# power_amplifier.net
KiCad netlist of a schematic drawn in Altium Designer
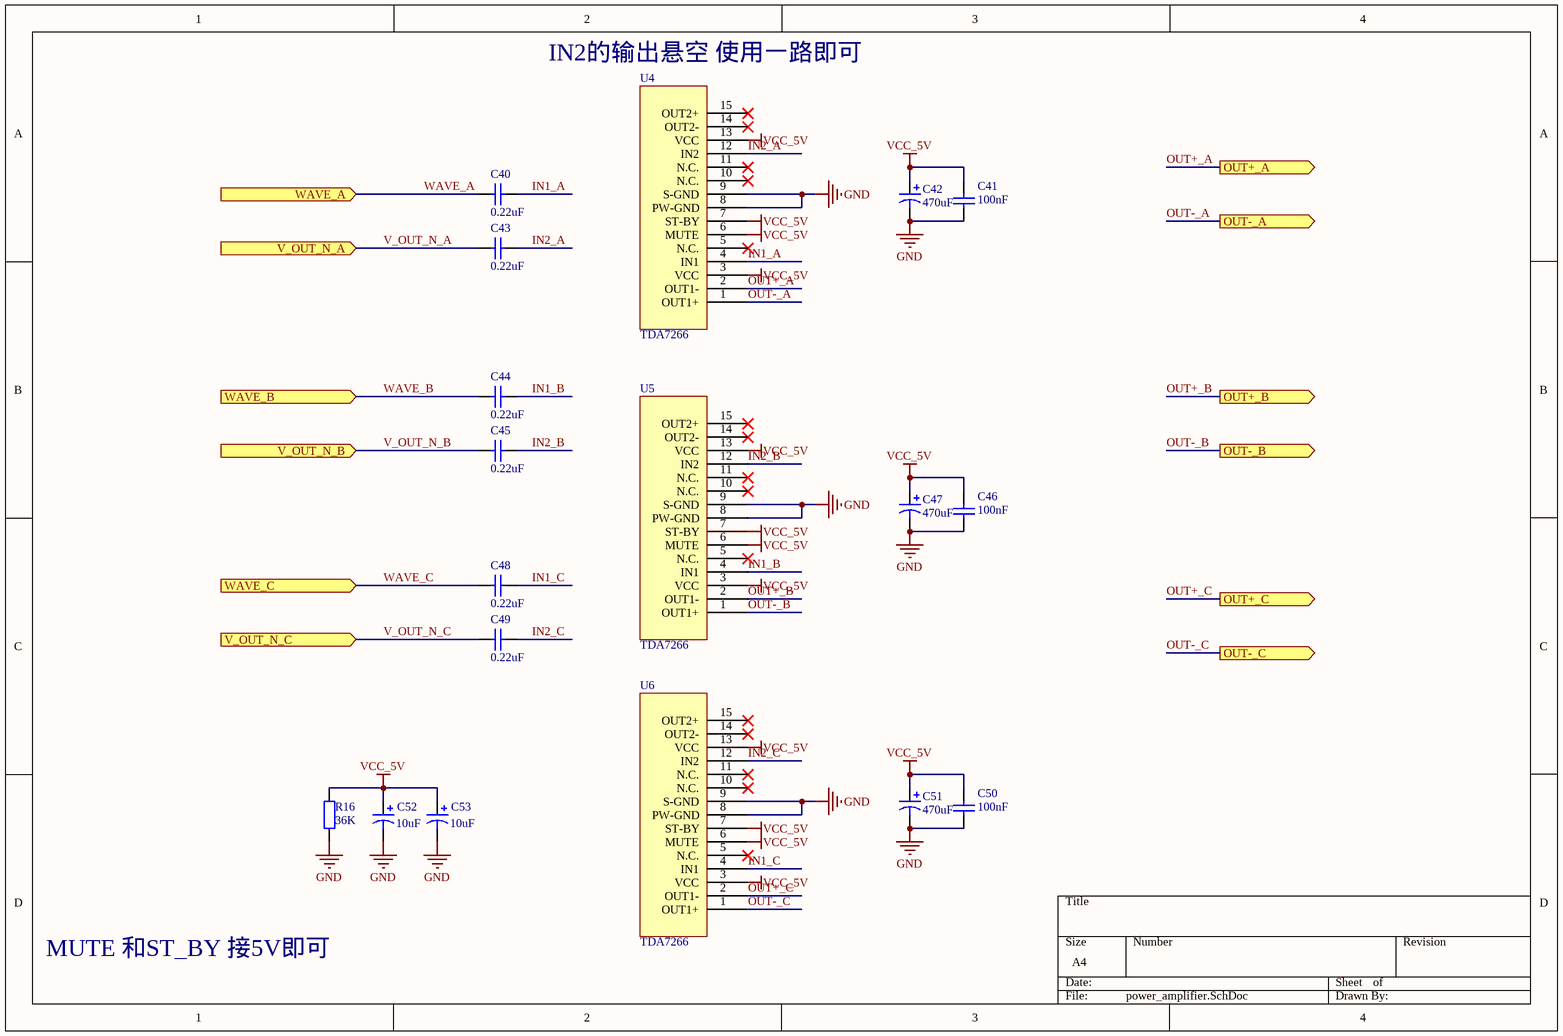
[diagram p0: power_amplifier.SchDoc]

(export (version "E")
  (design (tool "Eeschema 10.0.6"))
  (components
    (comp (ref "C40")
      (value "0.22uF")
      (footprint "0805")
      (fields
        (field (name "Comment") "Cap")
        (field (name "原理图绘制者") "刘永钦")
        (field (name "原理图提供者") "刘永钦")
        (field (name "原理图审核人1") "徐鹏飞")
        (field (name "封装0805绘制者") "刘永钦")
        (field (name "封装0805提供者") "刘永钦")
        (field (name "封装0805审核人1") "徐鹏飞")
        (field (name "原理图审核人2") "朱觉文")
        (field (name "封装0805审核人2") "朱觉文")
        (field (name "封装0603绘制者") "刘永钦")
        (field (name "封装0603提供者") "刘永钦")
        (field (name "封装0603审核人1") "朱觉文")
        (field (name "封装0603审核人2") "徐鹏飞")
      )
      (libsource (lib "自动化研究所集成库20170318") (part "Cap"))
    )
    (comp (ref "C41")
      (value "100nF")
      (footprint "0805")
      (fields
        (field (name "Comment") "Cap")
        (field (name "原理图绘制者") "刘永钦")
        (field (name "原理图提供者") "刘永钦")
        (field (name "原理图审核人1") "徐鹏飞")
        (field (name "封装0805绘制者") "刘永钦")
        (field (name "封装0805提供者") "刘永钦")
        (field (name "封装0805审核人1") "徐鹏飞")
        (field (name "原理图审核人2") "朱觉文")
        (field (name "封装0805审核人2") "朱觉文")
        (field (name "封装0603绘制者") "刘永钦")
        (field (name "封装0603提供者") "刘永钦")
        (field (name "封装0603审核人1") "朱觉文")
        (field (name "封装0603审核人2") "徐鹏飞")
      )
      (libsource (lib "自动化研究所集成库20170318") (part "Cap"))
    )
    (comp (ref "C42")
      (value "470uF")
      (footprint "cap贴片铝电解质470uF 16V")
      (fields
        (field (name "Comment") "Cap Poll")
        (field (name "原理图绘制者") "刘永钦")
        (field (name "原理图提供者") "刘永钦")
        (field (name "原理图审核人1") "徐鹏飞")
        (field (name "封装CAP 钽 7343 E绘制者") "刘永钦")
        (field (name "封装CAP 钽 7343 E提供者") "刘永钦")
        (field (name "封装CAP 钽 7343 E审核人1") "徐鹏飞")
        (field (name "封装CAP贴片铝电解质470UF 16V绘制者") "李泽")
        (field (name "封装CAP贴片铝电解质470UF 16V提供者") "刘永钦")
        (field (name "封装CAP贴片铝电解质470UF 16V审核人1") "徐鹏飞")
        (field (name "封装CAP 3528B绘制者") "陈汉诚")
        (field (name "封装CAP 3528B提供者") "刘永钦")
        (field (name "封装CAP 3528B审核人1") "徐鹏飞")
        (field (name "封装CAP直插 10UF 50V提供者") "刘永钦")
        (field (name "封装CAP直插 10UF 50V审核人1") "徐鹏飞")
        (field (name "封装CAP 3528B审核人2") "朱觉文")
        (field (name "封装CAP直插 10UF 50V审核人2") "朱觉文")
        (field (name "封装CAP贴片铝电解质470UF 16V审核人2") "朱觉文")
        (field (name "封装CAP 钽 7343 E审核人2") "朱觉文")
        (field (name "原理图审核人2") "朱觉文")
      )
      (libsource (lib "自动化研究所集成库20170318") (part "Cap Poll"))
    )
    (comp (ref "C43")
      (value "0.22uF")
      (footprint "0805")
      (fields
        (field (name "Comment") "Cap")
        (field (name "原理图绘制者") "刘永钦")
        (field (name "原理图提供者") "刘永钦")
        (field (name "原理图审核人1") "徐鹏飞")
        (field (name "封装0805绘制者") "刘永钦")
        (field (name "封装0805提供者") "刘永钦")
        (field (name "封装0805审核人1") "徐鹏飞")
        (field (name "原理图审核人2") "朱觉文")
        (field (name "封装0805审核人2") "朱觉文")
        (field (name "封装0603绘制者") "刘永钦")
        (field (name "封装0603提供者") "刘永钦")
        (field (name "封装0603审核人1") "朱觉文")
        (field (name "封装0603审核人2") "徐鹏飞")
      )
      (libsource (lib "自动化研究所集成库20170318") (part "Cap"))
    )
    (comp (ref "C44")
      (value "0.22uF")
      (footprint "0805")
      (fields
        (field (name "Comment") "Cap")
        (field (name "原理图绘制者") "刘永钦")
        (field (name "原理图提供者") "刘永钦")
        (field (name "原理图审核人1") "徐鹏飞")
        (field (name "封装0805绘制者") "刘永钦")
        (field (name "封装0805提供者") "刘永钦")
        (field (name "封装0805审核人1") "徐鹏飞")
        (field (name "原理图审核人2") "朱觉文")
        (field (name "封装0805审核人2") "朱觉文")
        (field (name "封装0603绘制者") "刘永钦")
        (field (name "封装0603提供者") "刘永钦")
        (field (name "封装0603审核人1") "朱觉文")
        (field (name "封装0603审核人2") "徐鹏飞")
      )
      (libsource (lib "自动化研究所集成库20170318") (part "Cap"))
    )
    (comp (ref "C45")
      (value "0.22uF")
      (footprint "0805")
      (fields
        (field (name "Comment") "Cap")
        (field (name "原理图绘制者") "刘永钦")
        (field (name "原理图提供者") "刘永钦")
        (field (name "原理图审核人1") "徐鹏飞")
        (field (name "封装0805绘制者") "刘永钦")
        (field (name "封装0805提供者") "刘永钦")
        (field (name "封装0805审核人1") "徐鹏飞")
        (field (name "原理图审核人2") "朱觉文")
        (field (name "封装0805审核人2") "朱觉文")
        (field (name "封装0603绘制者") "刘永钦")
        (field (name "封装0603提供者") "刘永钦")
        (field (name "封装0603审核人1") "朱觉文")
        (field (name "封装0603审核人2") "徐鹏飞")
      )
      (libsource (lib "自动化研究所集成库20170318") (part "Cap"))
    )
    (comp (ref "C46")
      (value "100nF")
      (footprint "0805")
      (fields
        (field (name "Comment") "Cap")
        (field (name "原理图绘制者") "刘永钦")
        (field (name "原理图提供者") "刘永钦")
        (field (name "原理图审核人1") "徐鹏飞")
        (field (name "封装0805绘制者") "刘永钦")
        (field (name "封装0805提供者") "刘永钦")
        (field (name "封装0805审核人1") "徐鹏飞")
        (field (name "原理图审核人2") "朱觉文")
        (field (name "封装0805审核人2") "朱觉文")
        (field (name "封装0603绘制者") "刘永钦")
        (field (name "封装0603提供者") "刘永钦")
        (field (name "封装0603审核人1") "朱觉文")
        (field (name "封装0603审核人2") "徐鹏飞")
      )
      (libsource (lib "自动化研究所集成库20170318") (part "Cap"))
    )
    (comp (ref "C47")
      (value "470uF")
      (footprint "cap贴片铝电解质470uF 16V")
      (fields
        (field (name "Comment") "Cap Poll")
        (field (name "原理图绘制者") "刘永钦")
        (field (name "原理图提供者") "刘永钦")
        (field (name "原理图审核人1") "徐鹏飞")
        (field (name "封装CAP 钽 7343 E绘制者") "刘永钦")
        (field (name "封装CAP 钽 7343 E提供者") "刘永钦")
        (field (name "封装CAP 钽 7343 E审核人1") "徐鹏飞")
        (field (name "封装CAP贴片铝电解质470UF 16V绘制者") "李泽")
        (field (name "封装CAP贴片铝电解质470UF 16V提供者") "刘永钦")
        (field (name "封装CAP贴片铝电解质470UF 16V审核人1") "徐鹏飞")
        (field (name "封装CAP 3528B绘制者") "陈汉诚")
        (field (name "封装CAP 3528B提供者") "刘永钦")
        (field (name "封装CAP 3528B审核人1") "徐鹏飞")
        (field (name "封装CAP直插 10UF 50V提供者") "刘永钦")
        (field (name "封装CAP直插 10UF 50V审核人1") "徐鹏飞")
        (field (name "封装CAP 3528B审核人2") "朱觉文")
        (field (name "封装CAP直插 10UF 50V审核人2") "朱觉文")
        (field (name "封装CAP贴片铝电解质470UF 16V审核人2") "朱觉文")
        (field (name "封装CAP 钽 7343 E审核人2") "朱觉文")
        (field (name "原理图审核人2") "朱觉文")
      )
      (libsource (lib "自动化研究所集成库20170318") (part "Cap Poll"))
    )
    (comp (ref "C48")
      (value "0.22uF")
      (footprint "0805")
      (fields
        (field (name "Comment") "Cap")
        (field (name "原理图绘制者") "刘永钦")
        (field (name "原理图提供者") "刘永钦")
        (field (name "原理图审核人1") "徐鹏飞")
        (field (name "封装0805绘制者") "刘永钦")
        (field (name "封装0805提供者") "刘永钦")
        (field (name "封装0805审核人1") "徐鹏飞")
        (field (name "原理图审核人2") "朱觉文")
        (field (name "封装0805审核人2") "朱觉文")
        (field (name "封装0603绘制者") "刘永钦")
        (field (name "封装0603提供者") "刘永钦")
        (field (name "封装0603审核人1") "朱觉文")
        (field (name "封装0603审核人2") "徐鹏飞")
      )
      (libsource (lib "自动化研究所集成库20170318") (part "Cap"))
    )
    (comp (ref "C49")
      (value "0.22uF")
      (footprint "0805")
      (fields
        (field (name "Comment") "Cap")
        (field (name "原理图绘制者") "刘永钦")
        (field (name "原理图提供者") "刘永钦")
        (field (name "原理图审核人1") "徐鹏飞")
        (field (name "封装0805绘制者") "刘永钦")
        (field (name "封装0805提供者") "刘永钦")
        (field (name "封装0805审核人1") "徐鹏飞")
        (field (name "原理图审核人2") "朱觉文")
        (field (name "封装0805审核人2") "朱觉文")
        (field (name "封装0603绘制者") "刘永钦")
        (field (name "封装0603提供者") "刘永钦")
        (field (name "封装0603审核人1") "朱觉文")
        (field (name "封装0603审核人2") "徐鹏飞")
      )
      (libsource (lib "自动化研究所集成库20170318") (part "Cap"))
    )
    (comp (ref "C50")
      (value "100nF")
      (footprint "0805")
      (fields
        (field (name "Comment") "Cap")
        (field (name "原理图绘制者") "刘永钦")
        (field (name "原理图提供者") "刘永钦")
        (field (name "原理图审核人1") "徐鹏飞")
        (field (name "封装0805绘制者") "刘永钦")
        (field (name "封装0805提供者") "刘永钦")
        (field (name "封装0805审核人1") "徐鹏飞")
        (field (name "原理图审核人2") "朱觉文")
        (field (name "封装0805审核人2") "朱觉文")
        (field (name "封装0603绘制者") "刘永钦")
        (field (name "封装0603提供者") "刘永钦")
        (field (name "封装0603审核人1") "朱觉文")
        (field (name "封装0603审核人2") "徐鹏飞")
      )
      (libsource (lib "自动化研究所集成库20170318") (part "Cap"))
    )
    (comp (ref "C51")
      (value "470uF")
      (footprint "cap贴片铝电解质470uF 16V")
      (fields
        (field (name "Comment") "Cap Poll")
        (field (name "原理图绘制者") "刘永钦")
        (field (name "原理图提供者") "刘永钦")
        (field (name "原理图审核人1") "徐鹏飞")
        (field (name "封装CAP 钽 7343 E绘制者") "刘永钦")
        (field (name "封装CAP 钽 7343 E提供者") "刘永钦")
        (field (name "封装CAP 钽 7343 E审核人1") "徐鹏飞")
        (field (name "封装CAP贴片铝电解质470UF 16V绘制者") "李泽")
        (field (name "封装CAP贴片铝电解质470UF 16V提供者") "刘永钦")
        (field (name "封装CAP贴片铝电解质470UF 16V审核人1") "徐鹏飞")
        (field (name "封装CAP 3528B绘制者") "陈汉诚")
        (field (name "封装CAP 3528B提供者") "刘永钦")
        (field (name "封装CAP 3528B审核人1") "徐鹏飞")
        (field (name "封装CAP直插 10UF 50V提供者") "刘永钦")
        (field (name "封装CAP直插 10UF 50V审核人1") "徐鹏飞")
        (field (name "封装CAP 3528B审核人2") "朱觉文")
        (field (name "封装CAP直插 10UF 50V审核人2") "朱觉文")
        (field (name "封装CAP贴片铝电解质470UF 16V审核人2") "朱觉文")
        (field (name "封装CAP 钽 7343 E审核人2") "朱觉文")
        (field (name "原理图审核人2") "朱觉文")
      )
      (libsource (lib "自动化研究所集成库20170318") (part "Cap Poll"))
    )
    (comp (ref "C52")
      (value "10uF")
      (footprint "Cap 3528B")
      (fields
        (field (name "Comment") "Cap Poll")
        (field (name "原理图绘制者") "刘永钦")
        (field (name "原理图提供者") "刘永钦")
        (field (name "原理图审核人1") "徐鹏飞")
        (field (name "封装CAP 钽 7343 E绘制者") "刘永钦")
        (field (name "封装CAP 钽 7343 E提供者") "刘永钦")
        (field (name "封装CAP 钽 7343 E审核人1") "徐鹏飞")
        (field (name "封装CAP贴片铝电解质470UF 16V绘制者") "李泽")
        (field (name "封装CAP贴片铝电解质470UF 16V提供者") "刘永钦")
        (field (name "封装CAP贴片铝电解质470UF 16V审核人1") "徐鹏飞")
        (field (name "封装CAP 3528B绘制者") "陈汉诚")
        (field (name "封装CAP 3528B提供者") "刘永钦")
        (field (name "封装CAP 3528B审核人1") "徐鹏飞")
        (field (name "封装CAP直插 10UF 50V提供者") "刘永钦")
        (field (name "封装CAP直插 10UF 50V审核人1") "徐鹏飞")
        (field (name "封装CAP 3528B审核人2") "朱觉文")
        (field (name "封装CAP直插 10UF 50V审核人2") "朱觉文")
        (field (name "封装CAP贴片铝电解质470UF 16V审核人2") "朱觉文")
        (field (name "封装CAP 钽 7343 E审核人2") "朱觉文")
        (field (name "原理图审核人2") "朱觉文")
      )
      (libsource (lib "自动化研究所集成库20170318") (part "Cap Poll"))
    )
    (comp (ref "C53")
      (value "10uF")
      (footprint "Cap 3528B")
      (fields
        (field (name "Comment") "Cap Poll")
        (field (name "原理图绘制者") "刘永钦")
        (field (name "原理图提供者") "刘永钦")
        (field (name "原理图审核人1") "徐鹏飞")
        (field (name "封装CAP 钽 7343 E绘制者") "刘永钦")
        (field (name "封装CAP 钽 7343 E提供者") "刘永钦")
        (field (name "封装CAP 钽 7343 E审核人1") "徐鹏飞")
        (field (name "封装CAP贴片铝电解质470UF 16V绘制者") "李泽")
        (field (name "封装CAP贴片铝电解质470UF 16V提供者") "刘永钦")
        (field (name "封装CAP贴片铝电解质470UF 16V审核人1") "徐鹏飞")
        (field (name "封装CAP 3528B绘制者") "陈汉诚")
        (field (name "封装CAP 3528B提供者") "刘永钦")
        (field (name "封装CAP 3528B审核人1") "徐鹏飞")
        (field (name "封装CAP直插 10UF 50V提供者") "刘永钦")
        (field (name "封装CAP直插 10UF 50V审核人1") "徐鹏飞")
        (field (name "封装CAP 3528B审核人2") "朱觉文")
        (field (name "封装CAP直插 10UF 50V审核人2") "朱觉文")
        (field (name "封装CAP贴片铝电解质470UF 16V审核人2") "朱觉文")
        (field (name "封装CAP 钽 7343 E审核人2") "朱觉文")
        (field (name "原理图审核人2") "朱觉文")
      )
      (libsource (lib "自动化研究所集成库20170318") (part "Cap Poll"))
    )
    (comp (ref "R16")
      (value "36K")
      (footprint "0805")
      (fields
        (field (name "Comment") "Res")
        (field (name "原理图绘制者") "刘永钦")
        (field (name "原理图提供者") "刘永钦")
        (field (name "原理图审核人1") "徐鹏飞")
        (field (name "封装0805绘制者") "刘永钦")
        (field (name "封装0805提供者") "刘永钦")
        (field (name "封装0805审核人1") "徐鹏飞")
        (field (name "原理图审核人2") "朱觉文")
        (field (name "封装0805审核人2") "朱觉文")
        (field (name "封装0603提供者") "刘永钦")
        (field (name "封装0603审核人2") "朱觉文")
        (field (name "封装0603审核人1") "徐鹏飞")
        (field (name "封装2512-RESC6332X06N审核人2") "朱觉文")
        (field (name "封装2512-RESC6332X06N提供者") "刘永钦")
        (field (name "封装2512-RESC6332X06N审核人1") "徐鹏飞")
        (field (name "封装0603绘制者") "刘永钦")
        (field (name "封装2512-RESC6332X06N绘制者") "刘永钦")
      )
      (libsource (lib "自动化研究所集成库20170318") (part "Res"))
    )
    (comp (ref "U4") (value "TDA7266") (footprint "TDA7266") (libsource (lib "Dugu") (part "TDA7266")))
    (comp (ref "U5") (value "TDA7266") (footprint "TDA7266") (libsource (lib "Dugu") (part "TDA7266")))
    (comp (ref "U6") (value "TDA7266") (footprint "TDA7266") (libsource (lib "Dugu") (part "TDA7266")))
  )
  (nets
    (net (code "1") (name "/IN1_A") (class "Default")
      (node (ref "C40") (pin "2") (pinfunction "2_2") (pintype "passive"))
      (node (ref "U4") (pin "4") (pinfunction "IN1_4") (pintype "passive"))
    )
    (net (code "2") (name "/IN1_B") (class "Default")
      (node (ref "C44") (pin "2") (pinfunction "2_2") (pintype "passive"))
      (node (ref "U5") (pin "4") (pinfunction "IN1_4") (pintype "passive"))
    )
    (net (code "3") (name "/IN1_C") (class "Default")
      (node (ref "C48") (pin "2") (pinfunction "2_2") (pintype "passive"))
      (node (ref "U6") (pin "4") (pinfunction "IN1_4") (pintype "passive"))
    )
    (net (code "4") (name "/IN2_A") (class "Default")
      (node (ref "C43") (pin "2") (pinfunction "2_2") (pintype "passive"))
      (node (ref "U4") (pin "12") (pinfunction "IN2_12") (pintype "passive"))
    )
    (net (code "5") (name "/IN2_B") (class "Default")
      (node (ref "C45") (pin "2") (pinfunction "2_2") (pintype "passive"))
      (node (ref "U5") (pin "12") (pinfunction "IN2_12") (pintype "passive"))
    )
    (net (code "6") (name "/IN2_C") (class "Default")
      (node (ref "C49") (pin "2") (pinfunction "2_2") (pintype "passive"))
      (node (ref "U6") (pin "12") (pinfunction "IN2_12") (pintype "passive"))
    )
    (net (code "7") (name "/OUT+_A") (class "Default")
      (node (ref "U4") (pin "2") (pinfunction "OUT1-_2") (pintype "passive"))
    )
    (net (code "8") (name "/OUT+_B") (class "Default")
      (node (ref "U5") (pin "2") (pinfunction "OUT1-_2") (pintype "passive"))
    )
    (net (code "9") (name "/OUT+_C") (class "Default")
      (node (ref "U6") (pin "2") (pinfunction "OUT1-_2") (pintype "passive"))
    )
    (net (code "10") (name "/OUT-_A") (class "Default")
      (node (ref "U4") (pin "1") (pinfunction "OUT1+_1") (pintype "passive"))
    )
    (net (code "11") (name "/OUT-_B") (class "Default")
      (node (ref "U5") (pin "1") (pinfunction "OUT1+_1") (pintype "passive"))
    )
    (net (code "12") (name "/OUT-_C") (class "Default")
      (node (ref "U6") (pin "1") (pinfunction "OUT1+_1") (pintype "passive"))
    )
    (net (code "13") (name "/V_OUT_N_A") (class "Default")
      (node (ref "C43") (pin "1") (pinfunction "1_1") (pintype "passive"))
    )
    (net (code "14") (name "/V_OUT_N_B") (class "Default")
      (node (ref "C45") (pin "1") (pinfunction "1_1") (pintype "passive"))
    )
    (net (code "15") (name "/V_OUT_N_C") (class "Default")
      (node (ref "C49") (pin "1") (pinfunction "1_1") (pintype "passive"))
    )
    (net (code "16") (name "/WAVE_A") (class "Default")
      (node (ref "C40") (pin "1") (pinfunction "1_1") (pintype "passive"))
    )
    (net (code "17") (name "/WAVE_B") (class "Default")
      (node (ref "C44") (pin "1") (pinfunction "1_1") (pintype "passive"))
    )
    (net (code "18") (name "/WAVE_C") (class "Default")
      (node (ref "C48") (pin "1") (pinfunction "1_1") (pintype "passive"))
    )
    (net (code "19") (name "GND") (class "Default")
      (node (ref "C41") (pin "1") (pinfunction "1_1") (pintype "passive"))
      (node (ref "C42") (pin "2") (pinfunction "2_2") (pintype "passive"))
      (node (ref "C46") (pin "1") (pinfunction "1_1") (pintype "passive"))
      (node (ref "C47") (pin "2") (pinfunction "2_2") (pintype "passive"))
      (node (ref "C50") (pin "1") (pinfunction "1_1") (pintype "passive"))
      (node (ref "C51") (pin "2") (pinfunction "2_2") (pintype "passive"))
      (node (ref "C52") (pin "2") (pinfunction "2_2") (pintype "passive"))
      (node (ref "C53") (pin "2") (pinfunction "2_2") (pintype "passive"))
      (node (ref "R16") (pin "1") (pinfunction "1_1") (pintype "passive"))
      (node (ref "U4") (pin "8") (pinfunction "PW-GND_8") (pintype "passive"))
      (node (ref "U4") (pin "9") (pinfunction "S-GND_9") (pintype "passive"))
      (node (ref "U5") (pin "8") (pinfunction "PW-GND_8") (pintype "passive"))
      (node (ref "U5") (pin "9") (pinfunction "S-GND_9") (pintype "passive"))
      (node (ref "U6") (pin "8") (pinfunction "PW-GND_8") (pintype "passive"))
      (node (ref "U6") (pin "9") (pinfunction "S-GND_9") (pintype "passive"))
    )
    (net (code "20") (name "VCC_5V") (class "Default")
      (node (ref "C41") (pin "2") (pinfunction "2_2") (pintype "passive"))
      (node (ref "C42") (pin "1") (pinfunction "1_1") (pintype "passive"))
      (node (ref "C46") (pin "2") (pinfunction "2_2") (pintype "passive"))
      (node (ref "C47") (pin "1") (pinfunction "1_1") (pintype "passive"))
      (node (ref "C50") (pin "2") (pinfunction "2_2") (pintype "passive"))
      (node (ref "C51") (pin "1") (pinfunction "1_1") (pintype "passive"))
      (node (ref "C52") (pin "1") (pinfunction "1_1") (pintype "passive"))
      (node (ref "C53") (pin "1") (pinfunction "1_1") (pintype "passive"))
      (node (ref "R16") (pin "2") (pinfunction "2_2") (pintype "passive"))
      (node (ref "U4") (pin "13") (pinfunction "VCC_13") (pintype "passive"))
      (node (ref "U4") (pin "3") (pinfunction "VCC_3") (pintype "passive"))
      (node (ref "U4") (pin "6") (pinfunction "MUTE_6") (pintype "passive"))
      (node (ref "U4") (pin "7") (pinfunction "ST-BY_7") (pintype "passive"))
      (node (ref "U5") (pin "13") (pinfunction "VCC_13") (pintype "passive"))
      (node (ref "U5") (pin "3") (pinfunction "VCC_3") (pintype "passive"))
      (node (ref "U5") (pin "6") (pinfunction "MUTE_6") (pintype "passive"))
      (node (ref "U5") (pin "7") (pinfunction "ST-BY_7") (pintype "passive"))
      (node (ref "U6") (pin "13") (pinfunction "VCC_13") (pintype "passive"))
      (node (ref "U6") (pin "3") (pinfunction "VCC_3") (pintype "passive"))
      (node (ref "U6") (pin "6") (pinfunction "MUTE_6") (pintype "passive"))
      (node (ref "U6") (pin "7") (pinfunction "ST-BY_7") (pintype "passive"))
    )
    (net (code "21") (name "unconnected-(U4-N.C.-Pad5)") (class "Default")
      (node (ref "U4") (pin "5") (pinfunction "N.C._5") (pintype "passive+no_connect"))
    )
    (net (code "22") (name "unconnected-(U4-N.C.-Pad10)") (class "Default")
      (node (ref "U4") (pin "10") (pinfunction "N.C._10") (pintype "passive+no_connect"))
    )
    (net (code "23") (name "unconnected-(U4-N.C.-Pad11)") (class "Default")
      (node (ref "U4") (pin "11") (pinfunction "N.C._11") (pintype "passive+no_connect"))
    )
    (net (code "24") (name "unconnected-(U4-OUT2+-Pad15)") (class "Default")
      (node (ref "U4") (pin "15") (pinfunction "OUT2+_15") (pintype "passive+no_connect"))
    )
    (net (code "25") (name "unconnected-(U4-OUT2--Pad14)") (class "Default")
      (node (ref "U4") (pin "14") (pinfunction "OUT2-_14") (pintype "passive+no_connect"))
    )
    (net (code "26") (name "unconnected-(U5-N.C.-Pad5)") (class "Default")
      (node (ref "U5") (pin "5") (pinfunction "N.C._5") (pintype "passive+no_connect"))
    )
    (net (code "27") (name "unconnected-(U5-N.C.-Pad10)") (class "Default")
      (node (ref "U5") (pin "10") (pinfunction "N.C._10") (pintype "passive+no_connect"))
    )
    (net (code "28") (name "unconnected-(U5-N.C.-Pad11)") (class "Default")
      (node (ref "U5") (pin "11") (pinfunction "N.C._11") (pintype "passive+no_connect"))
    )
    (net (code "29") (name "unconnected-(U5-OUT2+-Pad15)") (class "Default")
      (node (ref "U5") (pin "15") (pinfunction "OUT2+_15") (pintype "passive+no_connect"))
    )
    (net (code "30") (name "unconnected-(U5-OUT2--Pad14)") (class "Default")
      (node (ref "U5") (pin "14") (pinfunction "OUT2-_14") (pintype "passive+no_connect"))
    )
    (net (code "31") (name "unconnected-(U6-N.C.-Pad5)") (class "Default")
      (node (ref "U6") (pin "5") (pinfunction "N.C._5") (pintype "passive+no_connect"))
    )
    (net (code "32") (name "unconnected-(U6-N.C.-Pad10)") (class "Default")
      (node (ref "U6") (pin "10") (pinfunction "N.C._10") (pintype "passive+no_connect"))
    )
    (net (code "33") (name "unconnected-(U6-N.C.-Pad11)") (class "Default")
      (node (ref "U6") (pin "11") (pinfunction "N.C._11") (pintype "passive+no_connect"))
    )
    (net (code "34") (name "unconnected-(U6-OUT2+-Pad15)") (class "Default")
      (node (ref "U6") (pin "15") (pinfunction "OUT2+_15") (pintype "passive+no_connect"))
    )
    (net (code "35") (name "unconnected-(U6-OUT2--Pad14)") (class "Default")
      (node (ref "U6") (pin "14") (pinfunction "OUT2-_14") (pintype "passive+no_connect"))
    )
  )
)
